# touch_board.net
KiCad netlist of a schematic drawn in EAGLE
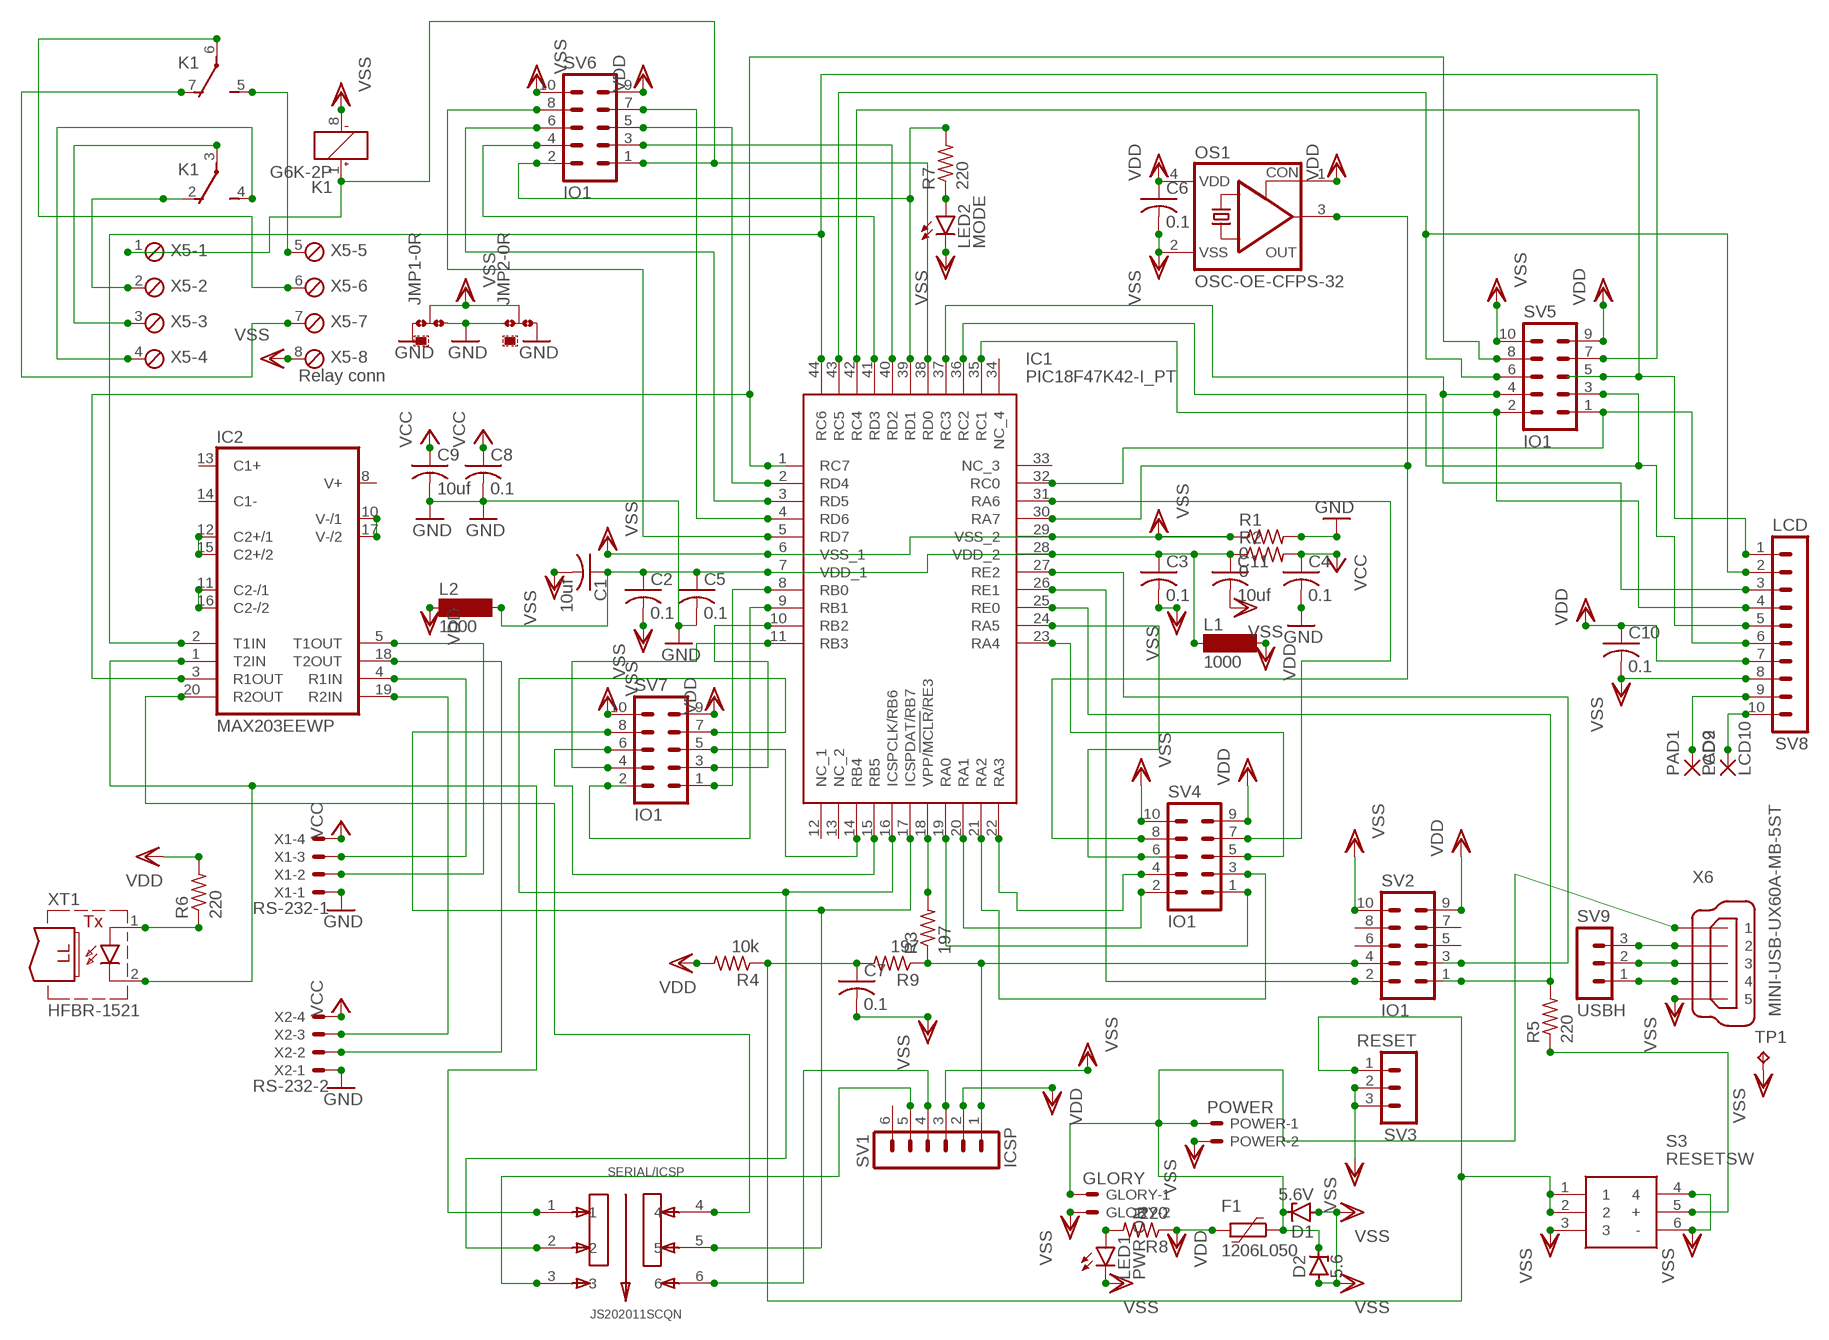
[diagram p0: schematic, sheet 1]

(export (version "E")
  (design (tool "Eeschema 10.0.6"))
  (components
    (comp (ref "C1")
      (value "10uf")
      (footprint "eagle-import:C0805")
      (libsource (lib "eagle-import") (part "C-USC0805"))
    )
    (comp (ref "C2")
      (value "0.1")
      (footprint "eagle-import:C0805")
      (libsource (lib "eagle-import") (part "C-USC0805"))
    )
    (comp (ref "C3")
      (value "0.1")
      (footprint "eagle-import:C0805")
      (libsource (lib "eagle-import") (part "C-USC0805"))
    )
    (comp (ref "C4")
      (value "0.1")
      (footprint "eagle-import:C0805")
      (libsource (lib "eagle-import") (part "C-USC0805"))
    )
    (comp (ref "C5")
      (value "0.1")
      (footprint "eagle-import:C0805")
      (libsource (lib "eagle-import") (part "C-USC0805"))
    )
    (comp (ref "C6")
      (value "0.1")
      (footprint "eagle-import:C0805")
      (libsource (lib "eagle-import") (part "C-USC0805"))
    )
    (comp (ref "C7")
      (value "0.1")
      (footprint "eagle-import:C0805")
      (libsource (lib "eagle-import") (part "C-USC0805"))
    )
    (comp (ref "C8")
      (value "0.1")
      (footprint "eagle-import:C0805")
      (libsource (lib "eagle-import") (part "C-USC0805"))
    )
    (comp (ref "C9")
      (value "10uf")
      (footprint "eagle-import:C0805")
      (libsource (lib "eagle-import") (part "C-USC0805"))
    )
    (comp (ref "C10")
      (value "0.1")
      (footprint "eagle-import:C0805")
      (libsource (lib "eagle-import") (part "C-USC0805"))
    )
    (comp (ref "C11")
      (value "10uf")
      (footprint "eagle-import:C0805")
      (libsource (lib "eagle-import") (part "C-USC0805"))
    )
    (comp (ref "D1")
      (value "5.6V")
      (footprint "eagle-import:ZDIO-7.5")
      (libsource (lib "eagle-import") (part "ZENER-DIODEZD-7.5"))
    )
    (comp (ref "D2")
      (value "5.6")
      (footprint "eagle-import:SMB")
      (libsource (lib "eagle-import") (part "ZENER-DIODESMB"))
    )
    (comp (ref "F1")
      (value "1206L050")
      (footprint "eagle-import:1206L")
      (fields (field (name "MF") "Littelfuse"))
      (libsource (lib "eagle-import") (part "?1206L050"))
    )
    (comp (ref "GLORY")
      (value "GLORY")
      (footprint "eagle-import:22-23-2021")
      (fields (field (name "MF") "MOLEX") (field (name "MPN") "22-23-2021"))
      (libsource (lib "eagle-import") (part "22-23-2021"))
    )
    (comp (ref "IC1")
      (value "PIC18F47K42-I_PT")
      (footprint "eagle-import:QFP80P1200X1200X120-44N")
      (fields
        (field (name "MANUFACTURER_PART_NUMBER") "PIC18F47K42-I/PT")
        (field (name "MOUSER_PART_NUMBER") "579-PIC18F47K42-I/PT")
      )
      (libsource (lib "eagle-import") (part "PIC18F47K42-I_PT"))
    )
    (comp (ref "IC2")
      (value "MAX203EEWP")
      (footprint "eagle-import:SO20L")
      (libsource (lib "eagle-import") (part "MAX203WPEE"))
    )
    (comp (ref "JMP1")
      (value "0R-JUMPA")
      (footprint "eagle-import:A0R-JMP")
      (libsource (lib "eagle-import") (part "0R-JUMPA"))
    )
    (comp (ref "JMP2")
      (value "0R-JUMPA")
      (footprint "eagle-import:A0R-JMP")
      (libsource (lib "eagle-import") (part "0R-JUMPA"))
    )
    (comp (ref "K1")
      (value "G6K-2P")
      (footprint "eagle-import:G6K-2P")
      (fields (field (name "MF") "OMRON COMPONENTS USA") (field (name "MPN") "G6K-2P DC3"))
      (libsource (lib "eagle-import") (part "G6K-2P"))
    )
    (comp (ref "L1")
      (value "1000")
      (footprint "eagle-import:SM-1206")
      (libsource (lib "eagle-import") (part "SM-1206"))
    )
    (comp (ref "L2")
      (value "1000")
      (footprint "eagle-import:SM-1206")
      (libsource (lib "eagle-import") (part "SM-1206"))
    )
    (comp (ref "LED1")
      (value "PWR ON")
      (footprint "eagle-import:CHIPLED_1206")
      (libsource (lib "eagle-import") (part "LEDCHIPLED_1206"))
    )
    (comp (ref "LED2")
      (value "MODE")
      (footprint "eagle-import:CHIPLED_1206")
      (libsource (lib "eagle-import") (part "LEDCHIPLED_1206"))
    )
    (comp (ref "OS1")
      (value "OSC-OE-CFPS-32")
      (footprint "eagle-import:7.2X5.2-4-PAD")
      (libsource (lib "eagle-import") (part "OSC-OE-CFPS-32"))
    )
    (comp (ref "PAD1")
      (value "LCD9")
      (footprint "eagle-import:SMD1,27-2,54")
      (libsource (lib "eagle-import") (part "SMD2"))
    )
    (comp (ref "PAD2")
      (value "LCD10")
      (footprint "eagle-import:SMD1,27-2,54")
      (libsource (lib "eagle-import") (part "SMD2"))
    )
    (comp (ref "POWER")
      (value "POWER")
      (footprint "eagle-import:22-23-2021")
      (fields (field (name "MF") "MOLEX") (field (name "MPN") "22-23-2021"))
      (libsource (lib "eagle-import") (part "22-23-2021"))
    )
    (comp (ref "R1")
      (value "0")
      (footprint "eagle-import:R0805")
      (libsource (lib "eagle-import") (part "R-US_R0805"))
    )
    (comp (ref "R2")
      (value "0")
      (footprint "eagle-import:R0805")
      (libsource (lib "eagle-import") (part "R-US_R0805"))
    )
    (comp (ref "R3")
      (value "197")
      (footprint "eagle-import:R0805")
      (libsource (lib "eagle-import") (part "R-US_R0805"))
    )
    (comp (ref "R4")
      (value "10k")
      (footprint "eagle-import:R0805")
      (libsource (lib "eagle-import") (part "R-US_R0805"))
    )
    (comp (ref "R5")
      (value "220")
      (footprint "eagle-import:R0805")
      (libsource (lib "eagle-import") (part "R-US_R0805"))
    )
    (comp (ref "R6")
      (value "220")
      (footprint "eagle-import:R0805")
      (libsource (lib "eagle-import") (part "R-US_R0805"))
    )
    (comp (ref "R7")
      (value "220")
      (footprint "eagle-import:R0805")
      (libsource (lib "eagle-import") (part "R-US_R0805"))
    )
    (comp (ref "R8")
      (value "220")
      (footprint "eagle-import:R0805")
      (libsource (lib "eagle-import") (part "R-US_R0805"))
    )
    (comp (ref "R9")
      (value "197")
      (footprint "eagle-import:R0805")
      (libsource (lib "eagle-import") (part "R-US_R0805"))
    )
    (comp (ref "S3")
      (value "RESETSW")
      (footprint "eagle-import:B3W-9_1-LED")
      (fields
        (field (name "MANUFACTURER_PART_NUMBER") "B3W-9000-Y1N")
        (field (name "MOUSER_PART_NUMBER") "653-B3W-9000-Y1N")
        (field (name "RS_PART_NUMBER") "0492777P")
      )
      (libsource (lib "eagle-import") (part "B3W-9000-Y1N"))
    )
    (comp (ref "SERIAL/ICSP")
      (value "JS202011SCQN")
      (footprint "eagle-import:SW_JS202011SCQN")
      (fields (field (name "MF") "C&K"))
      (libsource (lib "eagle-import") (part "JS202011SCQN"))
    )
    (comp (ref "SV1")
      (value "ICSP")
      (footprint "eagle-import:MA06-1")
      (libsource (lib "eagle-import") (part "MA06-1"))
    )
    (comp (ref "SV2")
      (value "IO1")
      (footprint "eagle-import:MA05-2")
      (libsource (lib "eagle-import") (part "MA05-2"))
    )
    (comp (ref "SV3")
      (value "RESET")
      (footprint "eagle-import:MA03-1")
      (libsource (lib "eagle-import") (part "MA03-1"))
    )
    (comp (ref "SV4")
      (value "IO1")
      (footprint "eagle-import:MA05-2")
      (libsource (lib "eagle-import") (part "MA05-2"))
    )
    (comp (ref "SV5")
      (value "IO1")
      (footprint "eagle-import:MA05-2")
      (libsource (lib "eagle-import") (part "MA05-2"))
    )
    (comp (ref "SV6")
      (value "IO1")
      (footprint "eagle-import:MA05-2")
      (libsource (lib "eagle-import") (part "MA05-2"))
    )
    (comp (ref "SV7")
      (value "IO1")
      (footprint "eagle-import:MA05-2")
      (libsource (lib "eagle-import") (part "MA05-2"))
    )
    (comp (ref "SV8")
      (value "LCD")
      (footprint "eagle-import:MA10-1")
      (libsource (lib "eagle-import") (part "MA10-1"))
    )
    (comp (ref "SV9")
      (value "USBH")
      (footprint "eagle-import:MA03-1")
      (libsource (lib "eagle-import") (part "MA03-1"))
    )
    (comp (ref "TP1")
      (value "TPB1,27")
      (footprint "eagle-import:B1,27")
      (libsource (lib "eagle-import") (part "TPB1,27"))
    )
    (comp (ref "X1")
      (value "RS-232-1")
      (footprint "eagle-import:22-23-2041")
      (fields (field (name "MF") "MOLEX") (field (name "MPN") "22-23-2041"))
      (libsource (lib "eagle-import") (part "22-23-2041"))
    )
    (comp (ref "X2")
      (value "RS-232-2")
      (footprint "eagle-import:22-23-2041")
      (fields (field (name "MF") "MOLEX") (field (name "MPN") "22-23-2041"))
      (libsource (lib "eagle-import") (part "22-23-2041"))
    )
    (comp (ref "X5")
      (value "Relay conn")
      (footprint "eagle-import:8POL254")
      (libsource (lib "eagle-import") (part "MPT8"))
    )
    (comp (ref "X6")
      (value "MINI-USB-UX60A-MB-5ST")
      (footprint "eagle-import:UX60A-MB-5ST")
      (libsource (lib "eagle-import") (part "MINI-USB-UX60A-MB-5ST"))
    )
    (comp (ref "XT1")
      (value "HFBR-1521")
      (footprint "eagle-import:HFBR-15X3")
      (fields (field (name "MF") "AGILENT TECHNOLOGIES"))
      (libsource (lib "eagle-import") (part "HFBR-1521"))
    )
  )
  (nets
    (net (code "1") (name "GND") (class "Default")
      (node (ref "C4") (pin "2") (pinfunction "2_2") (pintype "passive"))
      (node (ref "C5") (pin "2") (pinfunction "2_2") (pintype "passive"))
      (node (ref "C8") (pin "2") (pinfunction "2_2") (pintype "passive"))
      (node (ref "C9") (pin "2") (pinfunction "2_2") (pintype "passive"))
      (node (ref "JMP1") (pin "1") (pinfunction "1_1") (pintype "passive"))
      (node (ref "JMP1") (pin "3") (pinfunction "3_3") (pintype "passive"))
      (node (ref "JMP2") (pin "1") (pinfunction "1_1") (pintype "passive"))
      (node (ref "JMP2") (pin "3") (pinfunction "3_3") (pintype "passive"))
      (node (ref "R1") (pin "2") (pinfunction "2_2") (pintype "passive"))
      (node (ref "X1") (pin "1") (pinfunction "S_1") (pintype "passive"))
      (node (ref "X2") (pin "1") (pinfunction "S_1") (pintype "passive"))
    )
    (net (code "2") (name "Net-(C7-Pad1)") (class "Default")
      (node (ref "C7") (pin "1") (pinfunction "1_1") (pintype "passive"))
      (node (ref "R4") (pin "1") (pinfunction "1_1") (pintype "passive"))
      (node (ref "R9") (pin "2") (pinfunction "2_2") (pintype "passive"))
      (node (ref "S3") (pin "1") (pinfunction "1_1") (pintype "bidirectional"))
      (node (ref "S3") (pin "2") (pinfunction "2_2") (pintype "bidirectional"))
      (node (ref "SV3") (pin "1") (pinfunction "1_1") (pintype "passive"))
    )
    (net (code "3") (name "Net-(GLORYA-S)") (class "Default")
      (node (ref "D1") (pin "C") (pinfunction "C_C") (pintype "passive"))
      (node (ref "D2") (pin "C") (pinfunction "C_C") (pintype "passive"))
      (node (ref "F1") (pin "1") (pinfunction "1_1") (pintype "passive"))
      (node (ref "GLORY") (pin "1") (pinfunction "S_1") (pintype "passive"))
      (node (ref "POWER") (pin "1") (pinfunction "S_1") (pintype "passive"))
      (node (ref "X6") (pin "1") (pinfunction "1_1") (pintype "input"))
    )
    (net (code "4") (name "Net-(IC1-ICSPCLK{slash}RB6)") (class "Default")
      (node (ref "IC1") (pin "16") (pinfunction "ICSPCLK/RB6_16") (pintype "bidirectional"))
      (node (ref "SERIAL/ICSP") (pin "2") (pinfunction "2_2") (pintype "passive"))
      (node (ref "SV7") (pin "7") (pinfunction "7_7") (pintype "passive"))
    )
    (net (code "5") (name "Net-(IC1-ICSPDAT{slash}RB7)") (class "Default")
      (node (ref "IC1") (pin "17") (pinfunction "ICSPDAT/RB7_17") (pintype "bidirectional"))
      (node (ref "SERIAL/ICSP") (pin "5") (pinfunction "5_5") (pintype "passive"))
      (node (ref "SV7") (pin "8") (pinfunction "8_8") (pintype "passive"))
    )
    (net (code "6") (name "Net-(IC1-RA0)") (class "Default")
      (node (ref "IC1") (pin "19") (pinfunction "RA0_19") (pintype "bidirectional"))
      (node (ref "SV4") (pin "1") (pinfunction "1_1") (pintype "passive"))
    )
    (net (code "7") (name "Net-(IC1-RA1)") (class "Default")
      (node (ref "IC1") (pin "20") (pinfunction "RA1_20") (pintype "bidirectional"))
      (node (ref "SV4") (pin "2") (pinfunction "2_2") (pintype "passive"))
    )
    (net (code "8") (name "Net-(IC1-RA2)") (class "Default")
      (node (ref "IC1") (pin "21") (pinfunction "RA2_21") (pintype "bidirectional"))
      (node (ref "SV4") (pin "3") (pinfunction "3_3") (pintype "passive"))
    )
    (net (code "9") (name "Net-(IC1-RA3)") (class "Default")
      (node (ref "IC1") (pin "22") (pinfunction "RA3_22") (pintype "bidirectional"))
      (node (ref "SV4") (pin "4") (pinfunction "4_4") (pintype "passive"))
    )
    (net (code "10") (name "Net-(IC1-RA4)") (class "Default")
      (node (ref "IC1") (pin "23") (pinfunction "RA4_23") (pintype "bidirectional"))
      (node (ref "SV4") (pin "5") (pinfunction "5_5") (pintype "passive"))
    )
    (net (code "11") (name "Net-(IC1-RA5)") (class "Default")
      (node (ref "IC1") (pin "24") (pinfunction "RA5_24") (pintype "bidirectional"))
      (node (ref "SV4") (pin "6") (pinfunction "6_6") (pintype "passive"))
    )
    (net (code "12") (name "Net-(IC1-RA6)") (class "Default")
      (node (ref "IC1") (pin "31") (pinfunction "RA6_31") (pintype "bidirectional"))
      (node (ref "SV4") (pin "7") (pinfunction "7_7") (pintype "passive"))
    )
    (net (code "13") (name "Net-(IC1-RA7)") (class "Default")
      (node (ref "IC1") (pin "30") (pinfunction "RA7_30") (pintype "bidirectional"))
      (node (ref "OS1") (pin "3") (pinfunction "OUT_3") (pintype "output"))
      (node (ref "SV4") (pin "8") (pinfunction "8_8") (pintype "passive"))
    )
    (net (code "14") (name "Net-(IC1-RB0)") (class "Default")
      (node (ref "IC1") (pin "8") (pinfunction "RB0_8") (pintype "bidirectional"))
      (node (ref "SV7") (pin "1") (pinfunction "1_1") (pintype "passive"))
    )
    (net (code "15") (name "Net-(IC1-RB1)") (class "Default")
      (node (ref "IC1") (pin "9") (pinfunction "RB1_9") (pintype "bidirectional"))
      (node (ref "SV7") (pin "2") (pinfunction "2_2") (pintype "passive"))
    )
    (net (code "16") (name "Net-(IC1-RB2)") (class "Default")
      (node (ref "IC1") (pin "10") (pinfunction "RB2_10") (pintype "bidirectional"))
      (node (ref "SV7") (pin "3") (pinfunction "3_3") (pintype "passive"))
    )
    (net (code "17") (name "Net-(IC1-RB3)") (class "Default")
      (node (ref "IC1") (pin "11") (pinfunction "RB3_11") (pintype "bidirectional"))
      (node (ref "SV7") (pin "4") (pinfunction "4_4") (pintype "passive"))
    )
    (net (code "18") (name "Net-(IC1-RB4)") (class "Default")
      (node (ref "IC1") (pin "14") (pinfunction "RB4_14") (pintype "bidirectional"))
      (node (ref "SV7") (pin "5") (pinfunction "5_5") (pintype "passive"))
    )
    (net (code "19") (name "Net-(IC1-RB5)") (class "Default")
      (node (ref "IC1") (pin "15") (pinfunction "RB5_15") (pintype "bidirectional"))
      (node (ref "SV7") (pin "6") (pinfunction "6_6") (pintype "passive"))
    )
    (net (code "20") (name "Net-(IC1-RC0)") (class "Default")
      (node (ref "IC1") (pin "32") (pinfunction "RC0_32") (pintype "bidirectional"))
      (node (ref "SV5") (pin "1") (pinfunction "1_1") (pintype "passive"))
      (node (ref "SV8") (pin "6") (pinfunction "6_6") (pintype "passive"))
    )
    (net (code "21") (name "Net-(IC1-RC1)") (class "Default")
      (node (ref "IC1") (pin "35") (pinfunction "RC1_35") (pintype "bidirectional"))
      (node (ref "SV5") (pin "2") (pinfunction "2_2") (pintype "passive"))
      (node (ref "SV8") (pin "4") (pinfunction "4_4") (pintype "passive"))
    )
    (net (code "22") (name "Net-(IC1-RC2)") (class "Default")
      (node (ref "IC1") (pin "36") (pinfunction "RC2_36") (pintype "bidirectional"))
      (node (ref "SV5") (pin "3") (pinfunction "3_3") (pintype "passive"))
      (node (ref "SV8") (pin "5") (pinfunction "5_5") (pintype "passive"))
    )
    (net (code "23") (name "Net-(IC1-RC3)") (class "Default")
      (node (ref "IC1") (pin "37") (pinfunction "RC3_37") (pintype "bidirectional"))
      (node (ref "SV5") (pin "4") (pinfunction "4_4") (pintype "passive"))
      (node (ref "SV8") (pin "3") (pinfunction "3_3") (pintype "passive"))
    )
    (net (code "24") (name "Net-(IC1-RC4)") (class "Default")
      (node (ref "IC1") (pin "42") (pinfunction "RC4_42") (pintype "bidirectional"))
      (node (ref "SV5") (pin "5") (pinfunction "5_5") (pintype "passive"))
      (node (ref "SV8") (pin "1") (pinfunction "1_1") (pintype "passive"))
    )
    (net (code "25") (name "Net-(IC1-RC5)") (class "Default")
      (node (ref "IC1") (pin "43") (pinfunction "RC5_43") (pintype "bidirectional"))
      (node (ref "SV5") (pin "6") (pinfunction "6_6") (pintype "passive"))
      (node (ref "SV8") (pin "2") (pinfunction "2_2") (pintype "passive"))
    )
    (net (code "26") (name "Net-(IC1-RC6)") (class "Default")
      (node (ref "IC1") (pin "44") (pinfunction "RC6_44") (pintype "bidirectional"))
      (node (ref "IC2") (pin "2") (pinfunction "T1IN_2") (pintype "input"))
      (node (ref "SV5") (pin "7") (pinfunction "7_7") (pintype "passive"))
    )
    (net (code "27") (name "Net-(IC1-RC7)") (class "Default")
      (node (ref "IC1") (pin "1") (pinfunction "RC7_1") (pintype "bidirectional"))
      (node (ref "IC2") (pin "3") (pinfunction "R1OUT_3") (pintype "output"))
      (node (ref "SV5") (pin "8") (pinfunction "8_8") (pintype "passive"))
    )
    (net (code "28") (name "Net-(IC1-RD0)") (class "Default")
      (node (ref "IC1") (pin "38") (pinfunction "RD0_38") (pintype "bidirectional"))
      (node (ref "K1") (pin "1") (pinfunction "+_1") (pintype "passive"))
      (node (ref "SV6") (pin "1") (pinfunction "1_1") (pintype "passive"))
      (node (ref "X5") (pin "1") (pinfunction "1_1") (pintype "passive"))
    )
    (net (code "29") (name "Net-(IC1-RD1)") (class "Default")
      (node (ref "IC1") (pin "39") (pinfunction "RD1_39") (pintype "bidirectional"))
      (node (ref "R7") (pin "2") (pinfunction "2_2") (pintype "passive"))
      (node (ref "SV6") (pin "2") (pinfunction "2_2") (pintype "passive"))
    )
    (net (code "30") (name "Net-(IC1-RD2)") (class "Default")
      (node (ref "IC1") (pin "40") (pinfunction "RD2_40") (pintype "bidirectional"))
      (node (ref "SV6") (pin "3") (pinfunction "3_3") (pintype "passive"))
    )
    (net (code "31") (name "Net-(IC1-RD3)") (class "Default")
      (node (ref "IC1") (pin "41") (pinfunction "RD3_41") (pintype "bidirectional"))
      (node (ref "SV6") (pin "4") (pinfunction "4_4") (pintype "passive"))
    )
    (net (code "32") (name "Net-(IC1-RD4)") (class "Default")
      (node (ref "IC1") (pin "2") (pinfunction "RD4_2") (pintype "bidirectional"))
      (node (ref "SV6") (pin "5") (pinfunction "5_5") (pintype "passive"))
    )
    (net (code "33") (name "Net-(IC1-RD5)") (class "Default")
      (node (ref "IC1") (pin "3") (pinfunction "RD5_3") (pintype "bidirectional"))
      (node (ref "SV6") (pin "6") (pinfunction "6_6") (pintype "passive"))
    )
    (net (code "34") (name "Net-(IC1-RD6)") (class "Default")
      (node (ref "IC1") (pin "4") (pinfunction "RD6_4") (pintype "bidirectional"))
      (node (ref "SV6") (pin "7") (pinfunction "7_7") (pintype "passive"))
    )
    (net (code "35") (name "Net-(IC1-RD7)") (class "Default")
      (node (ref "IC1") (pin "5") (pinfunction "RD7_5") (pintype "bidirectional"))
      (node (ref "SV6") (pin "8") (pinfunction "8_8") (pintype "passive"))
    )
    (net (code "36") (name "Net-(IC1-RE0)") (class "Default")
      (node (ref "IC1") (pin "25") (pinfunction "RE0_25") (pintype "bidirectional"))
      (node (ref "R5") (pin "2") (pinfunction "2_2") (pintype "passive"))
      (node (ref "SV2") (pin "1") (pinfunction "1_1") (pintype "passive"))
    )
    (net (code "37") (name "Net-(IC1-RE1)") (class "Default")
      (node (ref "IC1") (pin "26") (pinfunction "RE1_26") (pintype "bidirectional"))
      (node (ref "SV2") (pin "2") (pinfunction "2_2") (pintype "passive"))
    )
    (net (code "38") (name "Net-(IC1-RE2)") (class "Default")
      (node (ref "IC1") (pin "27") (pinfunction "RE2_27") (pintype "bidirectional"))
      (node (ref "SV2") (pin "3") (pinfunction "3_3") (pintype "passive"))
    )
    (net (code "39") (name "Net-(IC1-VDD_1)") (class "Default")
      (node (ref "C1") (pin "1") (pinfunction "1_1") (pintype "passive"))
      (node (ref "C11") (pin "1") (pinfunction "1_1") (pintype "passive"))
      (node (ref "C2") (pin "1") (pinfunction "1_1") (pintype "passive"))
      (node (ref "C3") (pin "1") (pinfunction "1_1") (pintype "passive"))
      (node (ref "C5") (pin "1") (pinfunction "1_1") (pintype "passive"))
      (node (ref "IC1") (pin "28") (pinfunction "VDD_2_28") (pintype "bidirectional"))
      (node (ref "IC1") (pin "7") (pinfunction "VDD_1_7") (pintype "bidirectional"))
      (node (ref "L1") (pin "1") (pinfunction "1_1") (pintype "passive"))
      (node (ref "L2") (pin "2") (pinfunction "2_2") (pintype "passive"))
      (node (ref "R2") (pin "1") (pinfunction "1_1") (pintype "passive"))
    )
    (net (code "40") (name "Net-(IC1-VPP{slash}~{MCLR}{slash}RE3)") (class "Default")
      (node (ref "IC1") (pin "18") (pinfunction "VPP/~{MCLR}/RE3_18") (pintype "bidirectional"))
      (node (ref "R3") (pin "2") (pinfunction "2_2") (pintype "passive"))
    )
    (net (code "41") (name "Net-(IC2A-C2+{slash}1)") (class "Default")
      (node (ref "IC2") (pin "12") (pinfunction "C2+/1_12") (pintype "passive"))
      (node (ref "IC2") (pin "15") (pinfunction "C2+/2_15") (pintype "passive"))
    )
    (net (code "42") (name "Net-(IC2A-C2-{slash}1)") (class "Default")
      (node (ref "IC2") (pin "11") (pinfunction "C2-/1_11") (pintype "passive"))
      (node (ref "IC2") (pin "16") (pinfunction "C2-/2_16") (pintype "passive"))
    )
    (net (code "43") (name "Net-(IC2A-R1IN)") (class "Default")
      (node (ref "IC2") (pin "4") (pinfunction "R1IN_4") (pintype "input"))
      (node (ref "X1") (pin "3") (pinfunction "S_3") (pintype "passive"))
    )
    (net (code "44") (name "Net-(IC2A-R2IN)") (class "Default")
      (node (ref "IC2") (pin "19") (pinfunction "R2IN_19") (pintype "input"))
      (node (ref "X2") (pin "3") (pinfunction "S_3") (pintype "passive"))
    )
    (net (code "45") (name "Net-(IC2A-R2OUT)") (class "Default")
      (node (ref "IC2") (pin "20") (pinfunction "R2OUT_20") (pintype "output"))
      (node (ref "SERIAL/ICSP") (pin "4") (pinfunction "4_4") (pintype "passive"))
    )
    (net (code "46") (name "Net-(IC2A-T1OUT)") (class "Default")
      (node (ref "IC2") (pin "5") (pinfunction "T1OUT_5") (pintype "output"))
      (node (ref "X1") (pin "2") (pinfunction "S_2") (pintype "passive"))
    )
    (net (code "47") (name "Net-(IC2A-T2IN)") (class "Default")
      (node (ref "IC2") (pin "1") (pinfunction "T2IN_1") (pintype "input"))
      (node (ref "SERIAL/ICSP") (pin "1") (pinfunction "1_1") (pintype "passive"))
      (node (ref "XT1") (pin "2") (pinfunction "C_2") (pintype "passive"))
    )
    (net (code "48") (name "Net-(IC2A-T2OUT)") (class "Default")
      (node (ref "IC2") (pin "18") (pinfunction "T2OUT_18") (pintype "output"))
      (node (ref "X2") (pin "2") (pinfunction "S_2") (pintype "passive"))
    )
    (net (code "49") (name "Net-(IC2A-V-{slash}1)") (class "Default")
      (node (ref "IC2") (pin "10") (pinfunction "V-/1_10") (pintype "passive"))
      (node (ref "IC2") (pin "17") (pinfunction "V-/2_17") (pintype "passive"))
    )
    (net (code "50") (name "Net-(K1B-O)") (class "Default")
      (node (ref "K1") (pin "2") (pinfunction "O_2") (pintype "passive"))
      (node (ref "X5") (pin "2") (pinfunction "1_2") (pintype "passive"))
    )
    (net (code "51") (name "Net-(K1B-P)") (class "Default")
      (node (ref "K1") (pin "3") (pinfunction "P_3") (pintype "passive"))
      (node (ref "X5") (pin "3") (pinfunction "1_3") (pintype "passive"))
    )
    (net (code "52") (name "Net-(K1B-S)") (class "Default")
      (node (ref "K1") (pin "4") (pinfunction "S_4") (pintype "passive"))
      (node (ref "X5") (pin "4") (pinfunction "1_4") (pintype "passive"))
    )
    (net (code "53") (name "Net-(K1C-O)") (class "Default")
      (node (ref "K1") (pin "7") (pinfunction "O_7") (pintype "passive"))
      (node (ref "X5") (pin "7") (pinfunction "1_7") (pintype "passive"))
    )
    (net (code "54") (name "Net-(K1C-P)") (class "Default")
      (node (ref "K1") (pin "6") (pinfunction "P_6") (pintype "passive"))
      (node (ref "X5") (pin "6") (pinfunction "1_6") (pintype "passive"))
    )
    (net (code "55") (name "Net-(K1C-S)") (class "Default")
      (node (ref "K1") (pin "5") (pinfunction "S_5") (pintype "passive"))
      (node (ref "X5") (pin "5") (pinfunction "1_5") (pintype "passive"))
    )
    (net (code "56") (name "Net-(LED1-PadA)") (class "Default")
      (node (ref "LED1") (pin "A") (pinfunction "A_A") (pintype "passive"))
      (node (ref "R8") (pin "2") (pinfunction "2_2") (pintype "passive"))
    )
    (net (code "57") (name "Net-(LED2-PadA)") (class "Default")
      (node (ref "LED2") (pin "A") (pinfunction "A_A") (pintype "passive"))
      (node (ref "R7") (pin "1") (pinfunction "1_1") (pintype "passive"))
    )
    (net (code "58") (name "Net-(PAD1-P)") (class "Default")
      (node (ref "PAD1") (pin "1") (pinfunction "P_1") (pintype "passive"))
      (node (ref "SV8") (pin "9") (pinfunction "9_9") (pintype "passive"))
    )
    (net (code "59") (name "Net-(PAD2-P)") (class "Default")
      (node (ref "PAD2") (pin "1") (pinfunction "P_1") (pintype "passive"))
      (node (ref "SV8") (pin "10") (pinfunction "10_10") (pintype "passive"))
    )
    (net (code "60") (name "Net-(R3-Pad1)") (class "Default")
      (node (ref "R3") (pin "1") (pinfunction "1_1") (pintype "passive"))
      (node (ref "R9") (pin "1") (pinfunction "1_1") (pintype "passive"))
      (node (ref "SV1") (pin "1") (pinfunction "1_1") (pintype "passive"))
      (node (ref "SV2") (pin "4") (pinfunction "4_4") (pintype "passive"))
    )
    (net (code "61") (name "Net-(S3-+)") (class "Default")
      (node (ref "R5") (pin "1") (pinfunction "1_1") (pintype "passive"))
      (node (ref "S3") (pin "5") (pinfunction "+_5") (pintype "bidirectional"))
    )
    (net (code "62") (name "Net-(SERIAL/ICSP-Pad3)") (class "Default")
      (node (ref "SERIAL/ICSP") (pin "3") (pinfunction "3_3") (pintype "passive"))
      (node (ref "SV1") (pin "5") (pinfunction "5_5") (pintype "passive"))
    )
    (net (code "63") (name "Net-(SERIAL/ICSP-Pad6)") (class "Default")
      (node (ref "SERIAL/ICSP") (pin "6") (pinfunction "6_6") (pintype "passive"))
      (node (ref "SV1") (pin "4") (pinfunction "4_4") (pintype "passive"))
    )
    (net (code "64") (name "Net-(SV9-Pad1)") (class "Default")
      (node (ref "SV9") (pin "1") (pinfunction "1_1") (pintype "passive"))
      (node (ref "X6") (pin "4") (pinfunction "4_4") (pintype "input"))
    )
    (net (code "65") (name "Net-(SV9-Pad2)") (class "Default")
      (node (ref "SV9") (pin "2") (pinfunction "2_2") (pintype "passive"))
      (node (ref "X6") (pin "3") (pinfunction "3_3") (pintype "input"))
    )
    (net (code "66") (name "Net-(SV9-Pad3)") (class "Default")
      (node (ref "SV9") (pin "3") (pinfunction "3_3") (pintype "passive"))
      (node (ref "X6") (pin "2") (pinfunction "2_2") (pintype "input"))
    )
    (net (code "67") (name "Net-(XT1-A)") (class "Default")
      (node (ref "R6") (pin "1") (pinfunction "1_1") (pintype "passive"))
      (node (ref "XT1") (pin "1") (pinfunction "A_1") (pintype "passive"))
    )
    (net (code "68") (name "VCC") (class "Default")
      (node (ref "C4") (pin "1") (pinfunction "1_1") (pintype "passive"))
      (node (ref "C8") (pin "1") (pinfunction "1_1") (pintype "passive"))
      (node (ref "C9") (pin "1") (pinfunction "1_1") (pintype "passive"))
      (node (ref "R2") (pin "2") (pinfunction "2_2") (pintype "passive"))
      (node (ref "X1") (pin "4") (pinfunction "S_4") (pintype "passive"))
      (node (ref "X2") (pin "4") (pinfunction "S_4") (pintype "passive"))
    )
    (net (code "69") (name "VDD") (class "Default")
      (node (ref "C10") (pin "1") (pinfunction "1_1") (pintype "passive"))
      (node (ref "C6") (pin "1") (pinfunction "1_1") (pintype "passive"))
      (node (ref "F1") (pin "2") (pinfunction "2_2") (pintype "passive"))
      (node (ref "L1") (pin "2") (pinfunction "2_2") (pintype "passive"))
      (node (ref "L2") (pin "1") (pinfunction "1_1") (pintype "passive"))
      (node (ref "OS1") (pin "1") (pinfunction "CON_1") (pintype "input"))
      (node (ref "OS1") (pin "4") (pinfunction "VDD_4") (pintype "power_in"))
      (node (ref "R4") (pin "2") (pinfunction "2_2") (pintype "passive"))
      (node (ref "R6") (pin "2") (pinfunction "2_2") (pintype "passive"))
      (node (ref "R8") (pin "1") (pinfunction "1_1") (pintype "passive"))
      (node (ref "SV1") (pin "2") (pinfunction "2_2") (pintype "passive"))
      (node (ref "SV2") (pin "9") (pinfunction "9_9") (pintype "passive"))
      (node (ref "SV4") (pin "9") (pinfunction "9_9") (pintype "passive"))
      (node (ref "SV5") (pin "9") (pinfunction "9_9") (pintype "passive"))
      (node (ref "SV6") (pin "9") (pinfunction "9_9") (pintype "passive"))
      (node (ref "SV7") (pin "9") (pinfunction "9_9") (pintype "passive"))
      (node (ref "SV8") (pin "7") (pinfunction "7_7") (pintype "passive"))
    )
    (net (code "70") (name "VSS") (class "Default")
      (node (ref "C1") (pin "2") (pinfunction "2_2") (pintype "passive"))
      (node (ref "C10") (pin "2") (pinfunction "2_2") (pintype "passive"))
      (node (ref "C11") (pin "2") (pinfunction "2_2") (pintype "passive"))
      (node (ref "C2") (pin "2") (pinfunction "2_2") (pintype "passive"))
      (node (ref "C3") (pin "2") (pinfunction "2_2") (pintype "passive"))
      (node (ref "C6") (pin "2") (pinfunction "2_2") (pintype "passive"))
      (node (ref "C7") (pin "2") (pinfunction "2_2") (pintype "passive"))
      (node (ref "D1") (pin "A") (pinfunction "A_A") (pintype "passive"))
      (node (ref "D2") (pin "A") (pinfunction "A_A") (pintype "passive"))
      (node (ref "GLORY") (pin "2") (pinfunction "S_2") (pintype "passive"))
      (node (ref "IC1") (pin "29") (pinfunction "VSS_2_29") (pintype "bidirectional"))
      (node (ref "IC1") (pin "6") (pinfunction "VSS_1_6") (pintype "bidirectional"))
      (node (ref "JMP1") (pin "2") (pinfunction "2_2") (pintype "passive"))
      (node (ref "JMP2") (pin "2") (pinfunction "2_2") (pintype "passive"))
      (node (ref "K1") (pin "8") (pinfunction "-_8") (pintype "passive"))
      (node (ref "LED1") (pin "C") (pinfunction "C_C") (pintype "passive"))
      (node (ref "LED2") (pin "C") (pinfunction "C_C") (pintype "passive"))
      (node (ref "OS1") (pin "2") (pinfunction "VSS_2") (pintype "power_in"))
      (node (ref "POWER") (pin "2") (pinfunction "S_2") (pintype "passive"))
      (node (ref "R1") (pin "1") (pinfunction "1_1") (pintype "passive"))
      (node (ref "S3") (pin "3") (pinfunction "3_3") (pintype "bidirectional"))
      (node (ref "S3") (pin "4") (pinfunction "4_4") (pintype "bidirectional"))
      (node (ref "S3") (pin "6") (pinfunction "-_6") (pintype "bidirectional"))
      (node (ref "SV1") (pin "3") (pinfunction "3_3") (pintype "passive"))
      (node (ref "SV2") (pin "10") (pinfunction "10_10") (pintype "passive"))
      (node (ref "SV3") (pin "2") (pinfunction "2_2") (pintype "passive"))
      (node (ref "SV3") (pin "3") (pinfunction "3_3") (pintype "passive"))
      (node (ref "SV4") (pin "10") (pinfunction "10_10") (pintype "passive"))
      (node (ref "SV5") (pin "10") (pinfunction "10_10") (pintype "passive"))
      (node (ref "SV6") (pin "10") (pinfunction "10_10") (pintype "passive"))
      (node (ref "SV7") (pin "10") (pinfunction "10_10") (pintype "passive"))
      (node (ref "SV8") (pin "8") (pinfunction "8_8") (pintype "passive"))
      (node (ref "TP1") (pin "TP") (pinfunction "TP_TP") (pintype "input"))
      (node (ref "X5") (pin "8") (pinfunction "1_8") (pintype "passive"))
      (node (ref "X6") (pin "5") (pinfunction "5_5") (pintype "input"))
    )
    (net (code "71") (name "unconnected-(IC1-NC_1-Pad12)") (class "Default")
      (node (ref "IC1") (pin "12") (pinfunction "NC_1_12") (pintype "bidirectional"))
    )
    (net (code "72") (name "unconnected-(IC1-NC_2-Pad13)") (class "Default")
      (node (ref "IC1") (pin "13") (pinfunction "NC_2_13") (pintype "bidirectional"))
    )
    (net (code "73") (name "unconnected-(IC1-NC_3-Pad33)") (class "Default")
      (node (ref "IC1") (pin "33") (pinfunction "NC_3_33") (pintype "bidirectional"))
    )
    (net (code "74") (name "unconnected-(IC1-NC_4-Pad34)") (class "Default")
      (node (ref "IC1") (pin "34") (pinfunction "NC_4_34") (pintype "bidirectional"))
    )
    (net (code "75") (name "unconnected-(IC2A-C1+-Pad13)") (class "Default")
      (node (ref "IC2") (pin "13") (pinfunction "C1+_13") (pintype "passive"))
    )
    (net (code "76") (name "unconnected-(IC2A-C1--Pad14)") (class "Default")
      (node (ref "IC2") (pin "14") (pinfunction "C1-_14") (pintype "passive"))
    )
    (net (code "77") (name "unconnected-(IC2A-V+-Pad8)") (class "Default")
      (node (ref "IC2") (pin "8") (pinfunction "V+_8") (pintype "passive"))
    )
    (net (code "78") (name "unconnected-(SV1-Pad6)") (class "Default")
      (node (ref "SV1") (pin "6") (pinfunction "6_6") (pintype "passive"))
    )
    (net (code "79") (name "unconnected-(SV2-Pad5)") (class "Default")
      (node (ref "SV2") (pin "5") (pinfunction "5_5") (pintype "passive"))
    )
    (net (code "80") (name "unconnected-(SV2-Pad6)") (class "Default")
      (node (ref "SV2") (pin "6") (pinfunction "6_6") (pintype "passive"))
    )
    (net (code "81") (name "unconnected-(SV2-Pad7)") (class "Default")
      (node (ref "SV2") (pin "7") (pinfunction "7_7") (pintype "passive"))
    )
    (net (code "82") (name "unconnected-(SV2-Pad8)") (class "Default")
      (node (ref "SV2") (pin "8") (pinfunction "8_8") (pintype "passive"))
    )
  )
)
